# extension-board.net
KiCad netlist of a schematic drawn in EAGLE
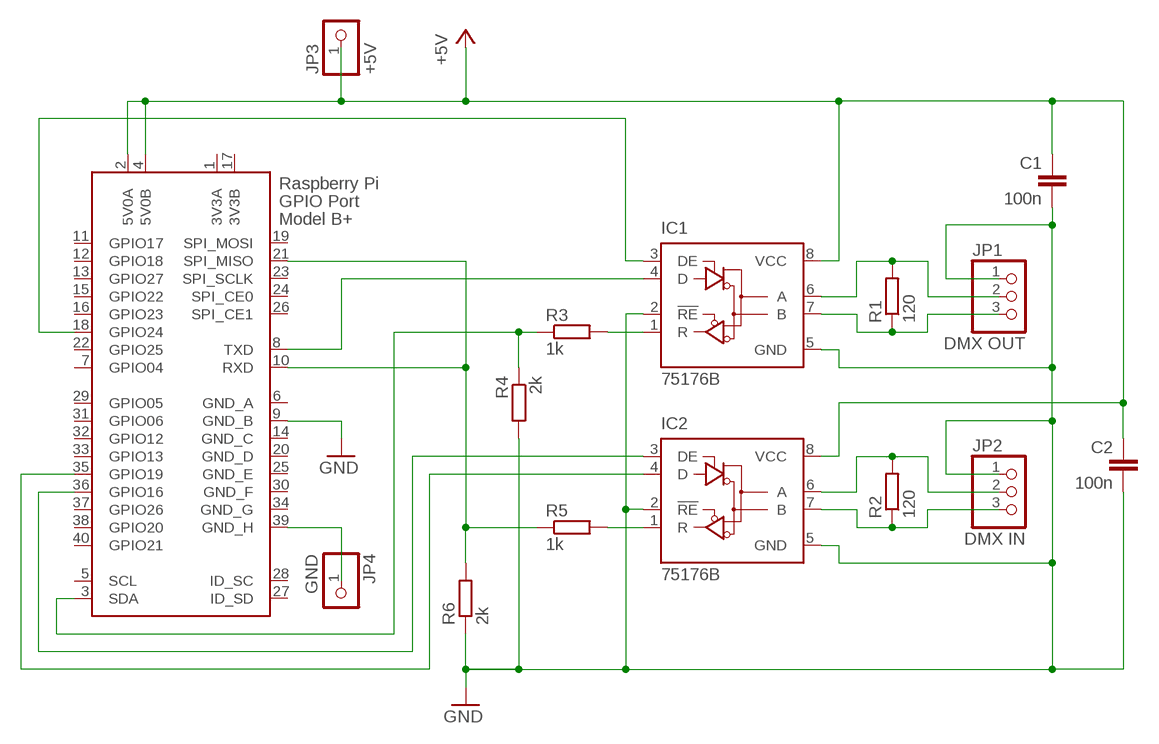
[diagram p0: schematic, sheet 1]

(export (version "E")
  (design (tool "Eeschema 10.0.6"))
  (components
    (comp (ref "C1")
      (value "100n")
      (footprint "eagle-import:C5B3")
      (libsource (lib "eagle-import") (part "C5/3"))
    )
    (comp (ref "C2")
      (value "100n")
      (footprint "eagle-import:C5B3")
      (libsource (lib "eagle-import") (part "C5/3"))
    )
    (comp (ref "IC1")
      (value "75176B")
      (footprint "eagle-import:DIL08")
      (libsource (lib "eagle-import") (part "75176AP"))
    )
    (comp (ref "IC2")
      (value "75176B")
      (footprint "eagle-import:DIL08")
      (libsource (lib "eagle-import") (part "75176AP"))
    )
    (comp (ref "JP1")
      (value "DMX OUT")
      (footprint "eagle-import:1X03")
      (libsource (lib "eagle-import") (part "PINHD-1X3"))
    )
    (comp (ref "JP2")
      (value "DMX IN")
      (footprint "eagle-import:1X03")
      (libsource (lib "eagle-import") (part "PINHD-1X3"))
    )
    (comp (ref "JP3")
      (value "+5V")
      (footprint "eagle-import:1X01")
      (libsource (lib "eagle-import") (part "PINHD-1X1"))
    )
    (comp (ref "JP4")
      (value "GND")
      (footprint "eagle-import:1X01")
      (libsource (lib "eagle-import") (part "PINHD-1X1"))
    )
    (comp (ref "R1")
      (value "120")
      (footprint "eagle-import:0204V")
      (libsource (lib "eagle-import") (part "R-EU_0204/2V"))
    )
    (comp (ref "R2")
      (value "120")
      (footprint "eagle-import:0204V")
      (libsource (lib "eagle-import") (part "R-EU_0204/2V"))
    )
    (comp (ref "R3")
      (value "1k")
      (footprint "eagle-import:0204_7")
      (libsource (lib "eagle-import") (part "R-EU_0204/7"))
    )
    (comp (ref "R4")
      (value "2k")
      (footprint "eagle-import:0204V")
      (libsource (lib "eagle-import") (part "R-EU_0204/2V"))
    )
    (comp (ref "R5")
      (value "1k")
      (footprint "eagle-import:0204_7")
      (libsource (lib "eagle-import") (part "R-EU_0204/7"))
    )
    (comp (ref "R6")
      (value "2k")
      (footprint "eagle-import:0204_7")
      (libsource (lib "eagle-import") (part "R-EU_0204/7"))
    )
    (comp (ref "X1")
      (value "RASPI_GPIO_B+#_PIN")
      (footprint "eagle-import:RASPI_GPIO_B+_PIN")
      (libsource (lib "eagle-import") (part "RASPI_GPIO_B+#_PIN"))
    )
  )
  (nets
    (net (code "1") (name "+5V") (class "Default")
      (node (ref "C1") (pin "1") (pinfunction "1_1") (pintype "passive"))
      (node (ref "C2") (pin "1") (pinfunction "1_1") (pintype "passive"))
      (node (ref "IC1") (pin "8") (pinfunction "VCC_8") (pintype "power_in"))
      (node (ref "IC2") (pin "8") (pinfunction "VCC_8") (pintype "power_in"))
      (node (ref "JP3") (pin "1") (pinfunction "1_1") (pintype "passive"))
      (node (ref "X1") (pin "2") (pinfunction "5V0A_2") (pintype "power_in"))
      (node (ref "X1") (pin "4") (pinfunction "5V0B_4") (pintype "power_in"))
    )
    (net (code "2") (name "/3V3A") (class "Default")
      (node (ref "X1") (pin "1") (pinfunction "3V3A_1") (pintype "power_in"))
    )
    (net (code "3") (name "/3V3B") (class "Default")
      (node (ref "X1") (pin "17") (pinfunction "3V3B_17") (pintype "power_in"))
    )
    (net (code "4") (name "/GND_A") (class "Default")
      (node (ref "X1") (pin "6") (pinfunction "GND_A_6") (pintype "power_in"))
    )
    (net (code "5") (name "/GND_C") (class "Default")
      (node (ref "X1") (pin "14") (pinfunction "GND_C_14") (pintype "power_in"))
    )
    (net (code "6") (name "/GND_D") (class "Default")
      (node (ref "X1") (pin "20") (pinfunction "GND_D_20") (pintype "power_in"))
    )
    (net (code "7") (name "/GND_E") (class "Default")
      (node (ref "X1") (pin "25") (pinfunction "GND_E_25") (pintype "power_in"))
    )
    (net (code "8") (name "/GND_F") (class "Default")
      (node (ref "X1") (pin "30") (pinfunction "GND_F_30") (pintype "power_in"))
    )
    (net (code "9") (name "/GND_G") (class "Default")
      (node (ref "X1") (pin "34") (pinfunction "GND_G_34") (pintype "power_in"))
    )
    (net (code "10") (name "GND") (class "Default")
      (node (ref "C1") (pin "2") (pinfunction "2_2") (pintype "passive"))
      (node (ref "C2") (pin "2") (pinfunction "2_2") (pintype "passive"))
      (node (ref "IC1") (pin "2") (pinfunction "~{RE}_2") (pintype "input"))
      (node (ref "IC1") (pin "5") (pinfunction "GND_5") (pintype "power_in"))
      (node (ref "IC2") (pin "2") (pinfunction "~{RE}_2") (pintype "input"))
      (node (ref "IC2") (pin "5") (pinfunction "GND_5") (pintype "power_in"))
      (node (ref "JP1") (pin "1") (pinfunction "1_1") (pintype "passive"))
      (node (ref "JP2") (pin "1") (pinfunction "1_1") (pintype "passive"))
      (node (ref "R4") (pin "2") (pinfunction "2_2") (pintype "passive"))
      (node (ref "R6") (pin "1") (pinfunction "1_1") (pintype "passive"))
      (node (ref "X1") (pin "9") (pinfunction "GND_B_9") (pintype "power_in"))
    )
    (net (code "11") (name "Net-(IC1-A)") (class "Default")
      (node (ref "IC1") (pin "6") (pinfunction "A_6") (pintype "output"))
      (node (ref "JP1") (pin "2") (pinfunction "2_2") (pintype "passive"))
      (node (ref "R1") (pin "2") (pinfunction "2_2") (pintype "passive"))
    )
    (net (code "12") (name "Net-(IC1-B)") (class "Default")
      (node (ref "IC1") (pin "7") (pinfunction "B_7") (pintype "output"))
      (node (ref "JP1") (pin "3") (pinfunction "3_3") (pintype "passive"))
      (node (ref "R1") (pin "1") (pinfunction "1_1") (pintype "passive"))
    )
    (net (code "13") (name "Net-(IC1-D)") (class "Default")
      (node (ref "IC1") (pin "4") (pinfunction "D_4") (pintype "input"))
      (node (ref "X1") (pin "8") (pinfunction "TXD_8") (pintype "bidirectional"))
    )
    (net (code "14") (name "Net-(IC1-DE)") (class "Default")
      (node (ref "IC1") (pin "3") (pinfunction "DE_3") (pintype "input"))
      (node (ref "X1") (pin "18") (pinfunction "GPIO24_18") (pintype "bidirectional"))
    )
    (net (code "15") (name "Net-(IC1-R)") (class "Default")
      (node (ref "IC1") (pin "1") (pinfunction "R_1") (pintype "input"))
      (node (ref "R3") (pin "2") (pinfunction "2_2") (pintype "passive"))
    )
    (net (code "16") (name "Net-(IC2-A)") (class "Default")
      (node (ref "IC2") (pin "6") (pinfunction "A_6") (pintype "output"))
      (node (ref "JP2") (pin "2") (pinfunction "2_2") (pintype "passive"))
      (node (ref "R2") (pin "2") (pinfunction "2_2") (pintype "passive"))
    )
    (net (code "17") (name "Net-(IC2-B)") (class "Default")
      (node (ref "IC2") (pin "7") (pinfunction "B_7") (pintype "output"))
      (node (ref "JP2") (pin "3") (pinfunction "3_3") (pintype "passive"))
      (node (ref "R2") (pin "1") (pinfunction "1_1") (pintype "passive"))
    )
    (net (code "18") (name "Net-(IC2-D)") (class "Default")
      (node (ref "IC2") (pin "4") (pinfunction "D_4") (pintype "input"))
      (node (ref "X1") (pin "35") (pinfunction "GPIO19_35") (pintype "bidirectional"))
    )
    (net (code "19") (name "Net-(IC2-DE)") (class "Default")
      (node (ref "IC2") (pin "3") (pinfunction "DE_3") (pintype "input"))
      (node (ref "X1") (pin "36") (pinfunction "GPIO16_36") (pintype "bidirectional"))
    )
    (net (code "20") (name "Net-(IC2-R)") (class "Default")
      (node (ref "IC2") (pin "1") (pinfunction "R_1") (pintype "input"))
      (node (ref "R5") (pin "2") (pinfunction "2_2") (pintype "passive"))
    )
    (net (code "21") (name "Net-(X1-GND_H)") (class "Default")
      (node (ref "JP4") (pin "1") (pinfunction "1_1") (pintype "passive"))
      (node (ref "X1") (pin "39") (pinfunction "GND_H_39") (pintype "power_in"))
    )
    (net (code "22") (name "Net-(X1-RXD)") (class "Default")
      (node (ref "R5") (pin "1") (pinfunction "1_1") (pintype "passive"))
      (node (ref "R6") (pin "2") (pinfunction "2_2") (pintype "passive"))
      (node (ref "X1") (pin "10") (pinfunction "RXD_10") (pintype "bidirectional"))
      (node (ref "X1") (pin "21") (pinfunction "SPI_MISO_21") (pintype "bidirectional"))
    )
    (net (code "23") (name "Net-(X1-SDA)") (class "Default")
      (node (ref "R3") (pin "1") (pinfunction "1_1") (pintype "passive"))
      (node (ref "R4") (pin "1") (pinfunction "1_1") (pintype "passive"))
      (node (ref "X1") (pin "3") (pinfunction "SDA_3") (pintype "bidirectional"))
    )
    (net (code "24") (name "unconnected-(X1-GPIO04-Pad7)") (class "Default")
      (node (ref "X1") (pin "7") (pinfunction "GPIO04_7") (pintype "bidirectional"))
    )
    (net (code "25") (name "unconnected-(X1-GPIO05-Pad29)") (class "Default")
      (node (ref "X1") (pin "29") (pinfunction "GPIO05_29") (pintype "bidirectional"))
    )
    (net (code "26") (name "unconnected-(X1-GPIO06-Pad31)") (class "Default")
      (node (ref "X1") (pin "31") (pinfunction "GPIO06_31") (pintype "bidirectional"))
    )
    (net (code "27") (name "unconnected-(X1-GPIO12-Pad32)") (class "Default")
      (node (ref "X1") (pin "32") (pinfunction "GPIO12_32") (pintype "bidirectional"))
    )
    (net (code "28") (name "unconnected-(X1-GPIO13-Pad33)") (class "Default")
      (node (ref "X1") (pin "33") (pinfunction "GPIO13_33") (pintype "bidirectional"))
    )
    (net (code "29") (name "unconnected-(X1-GPIO17-Pad11)") (class "Default")
      (node (ref "X1") (pin "11") (pinfunction "GPIO17_11") (pintype "bidirectional"))
    )
    (net (code "30") (name "unconnected-(X1-GPIO18-Pad12)") (class "Default")
      (node (ref "X1") (pin "12") (pinfunction "GPIO18_12") (pintype "bidirectional"))
    )
    (net (code "31") (name "unconnected-(X1-GPIO20-Pad38)") (class "Default")
      (node (ref "X1") (pin "38") (pinfunction "GPIO20_38") (pintype "bidirectional"))
    )
    (net (code "32") (name "unconnected-(X1-GPIO21-Pad40)") (class "Default")
      (node (ref "X1") (pin "40") (pinfunction "GPIO21_40") (pintype "bidirectional"))
    )
    (net (code "33") (name "unconnected-(X1-GPIO22-Pad15)") (class "Default")
      (node (ref "X1") (pin "15") (pinfunction "GPIO22_15") (pintype "bidirectional"))
    )
    (net (code "34") (name "unconnected-(X1-GPIO23-Pad16)") (class "Default")
      (node (ref "X1") (pin "16") (pinfunction "GPIO23_16") (pintype "bidirectional"))
    )
    (net (code "35") (name "unconnected-(X1-GPIO25-Pad22)") (class "Default")
      (node (ref "X1") (pin "22") (pinfunction "GPIO25_22") (pintype "bidirectional"))
    )
    (net (code "36") (name "unconnected-(X1-GPIO26-Pad37)") (class "Default")
      (node (ref "X1") (pin "37") (pinfunction "GPIO26_37") (pintype "bidirectional"))
    )
    (net (code "37") (name "unconnected-(X1-GPIO27-Pad13)") (class "Default")
      (node (ref "X1") (pin "13") (pinfunction "GPIO27_13") (pintype "bidirectional"))
    )
    (net (code "38") (name "unconnected-(X1-ID_SC-Pad28)") (class "Default")
      (node (ref "X1") (pin "28") (pinfunction "ID_SC_28") (pintype "bidirectional"))
    )
    (net (code "39") (name "unconnected-(X1-ID_SD-Pad27)") (class "Default")
      (node (ref "X1") (pin "27") (pinfunction "ID_SD_27") (pintype "bidirectional"))
    )
    (net (code "40") (name "unconnected-(X1-SCL-Pad5)") (class "Default")
      (node (ref "X1") (pin "5") (pinfunction "SCL_5") (pintype "bidirectional"))
    )
    (net (code "41") (name "unconnected-(X1-SPI_CE0-Pad24)") (class "Default")
      (node (ref "X1") (pin "24") (pinfunction "SPI_CE0_24") (pintype "bidirectional"))
    )
    (net (code "42") (name "unconnected-(X1-SPI_CE1-Pad26)") (class "Default")
      (node (ref "X1") (pin "26") (pinfunction "SPI_CE1_26") (pintype "bidirectional"))
    )
    (net (code "43") (name "unconnected-(X1-SPI_MOSI-Pad19)") (class "Default")
      (node (ref "X1") (pin "19") (pinfunction "SPI_MOSI_19") (pintype "bidirectional"))
    )
    (net (code "44") (name "unconnected-(X1-SPI_SCLK-Pad23)") (class "Default")
      (node (ref "X1") (pin "23") (pinfunction "SPI_SCLK_23") (pintype "bidirectional"))
    )
  )
)
